# Sensor.net
KiCad netlist of a schematic drawn in Altium Designer
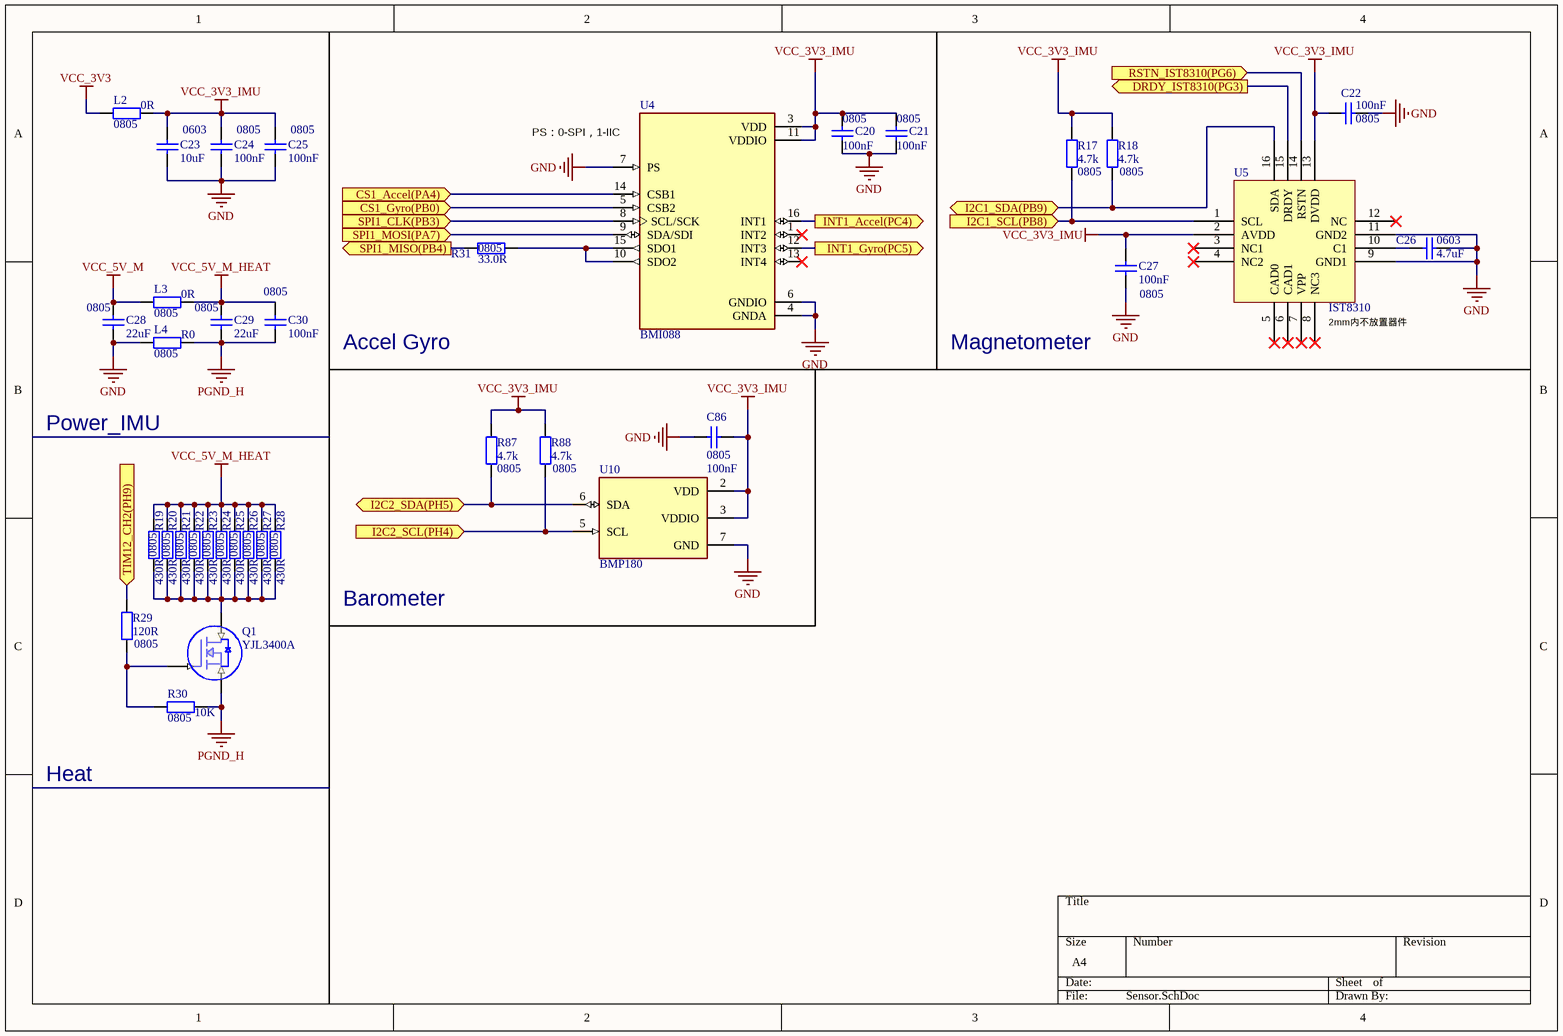
[diagram p0: Sensor.SchDoc]

(export (version "E")
  (design (tool "Eeschema 10.0.6"))
  (components
    (comp (ref "C20")
      (value "0805")
      (footprint "C 0805_M")
      (fields (field (name "ALTIUM_VALUE") "100nF"))
      (libsource (lib "QT") (part "CAP"))
    )
    (comp (ref "C21")
      (value "0805")
      (footprint "C 0805_M")
      (fields (field (name "ALTIUM_VALUE") "100nF"))
      (libsource (lib "QT") (part "CAP"))
    )
    (comp (ref "C22")
      (value "0805")
      (footprint "C 0805_M")
      (fields (field (name "ALTIUM_VALUE") "100nF"))
      (libsource (lib "QT") (part "CAP"))
    )
    (comp (ref "C23")
      (value "0603")
      (footprint "C 0603_L")
      (fields (field (name "ALTIUM_VALUE") "10uF"))
      (libsource (lib "QT") (part "CAP"))
    )
    (comp (ref "C24")
      (value "0805")
      (footprint "C 0805_M")
      (fields (field (name "ALTIUM_VALUE") "100nF"))
      (libsource (lib "QT") (part "CAP"))
    )
    (comp (ref "C25")
      (value "0805")
      (footprint "C 0805_M")
      (fields (field (name "ALTIUM_VALUE") "100nF"))
      (libsource (lib "QT") (part "CAP"))
    )
    (comp (ref "C26")
      (value "0603")
      (footprint "C 0603_M")
      (fields (field (name "ALTIUM_VALUE") "4.7uF"))
      (libsource (lib "QT") (part "CAP"))
    )
    (comp (ref "C27")
      (value "0805")
      (footprint "C 0805_M")
      (fields (field (name "ALTIUM_VALUE") "100nF"))
      (libsource (lib "QT") (part "CAP"))
    )
    (comp (ref "C28")
      (value "0805")
      (footprint "C 0805_L")
      (fields (field (name "ALTIUM_VALUE") "22uF"))
      (libsource (lib "QT") (part "CAP"))
    )
    (comp (ref "C29")
      (value "0805")
      (footprint "C 0805_L")
      (fields (field (name "ALTIUM_VALUE") "22uF"))
      (libsource (lib "QT") (part "CAP"))
    )
    (comp (ref "C30")
      (value "0805")
      (footprint "C 0805_M")
      (fields (field (name "ALTIUM_VALUE") "100nF"))
      (libsource (lib "QT") (part "CAP"))
    )
    (comp (ref "C86")
      (value "0805")
      (footprint "C 0805_M")
      (fields (field (name "ALTIUM_VALUE") "100nF"))
      (libsource (lib "QT") (part "CAP"))
    )
    (comp (ref "L2")
      (value "0805")
      (footprint "R 0805_L")
      (description "Resistor")
      (fields (field (name "ALTIUM_VALUE") "0R") (field (name "PUBLISHER") "Altium Limited"))
      (libsource (lib "") (part "RES2_2"))
    )
    (comp (ref "L3")
      (value "0805")
      (footprint "R 0805_L")
      (description "Resistor")
      (fields (field (name "ALTIUM_VALUE") "0R") (field (name "PUBLISHER") "Altium Limited"))
      (libsource (lib "") (part "RES2_2"))
    )
    (comp (ref "L4")
      (value "0805")
      (footprint "R 0805_L")
      (description "Resistor")
      (fields (field (name "ALTIUM_VALUE") "R0") (field (name "PUBLISHER") "Altium Limited"))
      (libsource (lib "") (part "RES2_2"))
    )
    (comp (ref "Q1") (value "YJL3400A") (footprint "SOT23-3M") (libsource (lib "场效应管及可控硅") (part "MOSFET N")))
    (comp (ref "R17")
      (value "0805")
      (footprint "R 0805_L")
      (description "Resistor")
      (fields (field (name "ALTIUM_VALUE") "4.7k") (field (name "PUBLISHER") "Altium Limited"))
      (libsource (lib "QT") (part "RES2"))
    )
    (comp (ref "R18")
      (value "0805")
      (footprint "R 0805_L")
      (description "Resistor")
      (fields (field (name "ALTIUM_VALUE") "4.7k") (field (name "PUBLISHER") "Altium Limited"))
      (libsource (lib "QT") (part "RES2"))
    )
    (comp (ref "R19")
      (value "0805")
      (footprint "R 0805_L")
      (description "Resistor")
      (fields (field (name "ALTIUM_VALUE") "430R") (field (name "PUBLISHER") "Altium Limited"))
      (libsource (lib "QT") (part "RES2"))
    )
    (comp (ref "R20")
      (value "0805")
      (footprint "R 0805_L")
      (description "Resistor")
      (fields (field (name "ALTIUM_VALUE") "430R") (field (name "PUBLISHER") "Altium Limited"))
      (libsource (lib "QT") (part "RES2"))
    )
    (comp (ref "R21")
      (value "0805")
      (footprint "R 0805_L")
      (description "Resistor")
      (fields (field (name "ALTIUM_VALUE") "430R") (field (name "PUBLISHER") "Altium Limited"))
      (libsource (lib "QT") (part "RES2"))
    )
    (comp (ref "R22")
      (value "0805")
      (footprint "R 0805_L")
      (description "Resistor")
      (fields (field (name "ALTIUM_VALUE") "430R") (field (name "PUBLISHER") "Altium Limited"))
      (libsource (lib "QT") (part "RES2"))
    )
    (comp (ref "R23")
      (value "0805")
      (footprint "R 0805_L")
      (description "Resistor")
      (fields (field (name "ALTIUM_VALUE") "430R") (field (name "PUBLISHER") "Altium Limited"))
      (libsource (lib "QT") (part "RES2"))
    )
    (comp (ref "R24")
      (value "0805")
      (footprint "R 0805_L")
      (description "Resistor")
      (fields (field (name "ALTIUM_VALUE") "430R") (field (name "PUBLISHER") "Altium Limited"))
      (libsource (lib "QT") (part "RES2"))
    )
    (comp (ref "R25")
      (value "0805")
      (footprint "R 0805_L")
      (description "Resistor")
      (fields (field (name "ALTIUM_VALUE") "430R") (field (name "PUBLISHER") "Altium Limited"))
      (libsource (lib "QT") (part "RES2"))
    )
    (comp (ref "R26")
      (value "0805")
      (footprint "R 0805_L")
      (description "Resistor")
      (fields (field (name "ALTIUM_VALUE") "430R") (field (name "PUBLISHER") "Altium Limited"))
      (libsource (lib "QT") (part "RES2"))
    )
    (comp (ref "R27")
      (value "0805")
      (footprint "R 0805_L")
      (description "Resistor")
      (fields (field (name "ALTIUM_VALUE") "430R") (field (name "PUBLISHER") "Altium Limited"))
      (libsource (lib "QT") (part "RES2"))
    )
    (comp (ref "R28")
      (value "0805")
      (footprint "R 0805_L")
      (description "Resistor")
      (fields (field (name "ALTIUM_VALUE") "430R") (field (name "PUBLISHER") "Altium Limited"))
      (libsource (lib "QT") (part "RES2"))
    )
    (comp (ref "R29")
      (value "0805")
      (footprint "R 0805_L")
      (description "Resistor")
      (fields (field (name "ALTIUM_VALUE") "120R") (field (name "PUBLISHER") "Altium Limited"))
      (libsource (lib "") (part "RES2_1"))
    )
    (comp (ref "R30")
      (value "0805")
      (footprint "R 0805_L")
      (description "Resistor")
      (fields (field (name "ALTIUM_VALUE") "10K") (field (name "PUBLISHER") "Altium Limited"))
      (libsource (lib "") (part "RES2_3"))
    )
    (comp (ref "R31")
      (value "0805")
      (footprint "R 0805_L")
      (description "Resistor")
      (fields (field (name "ALTIUM_VALUE") "33.0R") (field (name "PUBLISHER") "Altium Limited"))
      (libsource (lib "") (part "RES2_2"))
    )
    (comp (ref "R87")
      (value "0805")
      (footprint "R 0805_L")
      (description "Resistor")
      (fields (field (name "ALTIUM_VALUE") "4.7k") (field (name "PUBLISHER") "Altium Limited"))
      (libsource (lib "QT") (part "RES2"))
    )
    (comp (ref "R88")
      (value "0805")
      (footprint "R 0805_L")
      (description "Resistor")
      (fields (field (name "ALTIUM_VALUE") "4.7k") (field (name "PUBLISHER") "Altium Limited"))
      (libsource (lib "QT") (part "RES2"))
    )
    (comp (ref "U4")
      (value "BMI088")
      (footprint "PQFN50P450X300X100-16N")
      (description "Accelerometer, Gyroscope, 6 Axis Sensor IÂ²C, SPI Output")
      (fields (field (name "MF") "Bosch Sensortec"))
      (libsource (lib "BMI088") (part "BMI088"))
    )
    (comp (ref "U5") (value "IST8310") (footprint "QFN16") (libsource (lib "常用元件库") (part "IST8310")))
    (comp (ref "U10")
      (value "BMP180")
      (footprint "BMP180")
      (description "Pressure Sensor 4.35PSI ~ 15.95PSI _30kPa ~ 110kPa_ Absolute 16 ~ 19 b 7-VLGA")
      (fields (field (name "MF") "Bosch Sensortec") (field (name "DIGI-KEY_PART_NUMBER") "828-1027-1-ND"))
      (libsource (lib "BMP180") (part "BMP180"))
    )
  )
  (nets
    (net (code "1") (name "/CS1_Accel(PA4)") (class "Default")
      (node (ref "U4") (pin "14") (pinfunction "CSB1_14") (pintype "input"))
    )
    (net (code "2") (name "/CS1_Gyro(PB0)") (class "Default")
      (node (ref "U4") (pin "5") (pinfunction "CSB2_5") (pintype "input"))
    )
    (net (code "3") (name "/DRDY_IST8310(PG3)") (class "Default")
      (node (ref "U5") (pin "15") (pinfunction "DRDY_15") (pintype "passive"))
    )
    (net (code "4") (name "/I2C1_SCL(PB8)") (class "Default")
      (node (ref "R17") (pin "1") (pinfunction "1_1") (pintype "passive"))
      (node (ref "U5") (pin "1") (pinfunction "SCL_1") (pintype "passive"))
    )
    (net (code "5") (name "/I2C1_SDA(PB9)") (class "Default")
      (node (ref "R18") (pin "1") (pinfunction "1_1") (pintype "passive"))
      (node (ref "U5") (pin "16") (pinfunction "SDA_16") (pintype "passive"))
    )
    (net (code "6") (name "/I2C2_SCL(PH4)") (class "Default")
      (node (ref "R88") (pin "1") (pinfunction "1_1") (pintype "passive"))
      (node (ref "U10") (pin "5") (pinfunction "SCL_5") (pintype "input"))
    )
    (net (code "7") (name "/I2C2_SDA(PH5)") (class "Default")
      (node (ref "R87") (pin "1") (pinfunction "1_1") (pintype "passive"))
      (node (ref "U10") (pin "6") (pinfunction "SDA_6") (pintype "bidirectional"))
    )
    (net (code "8") (name "/INT1_Accel(PC4)") (class "Default")
      (node (ref "U4") (pin "16") (pinfunction "INT1_16") (pintype "bidirectional"))
    )
    (net (code "9") (name "/INT1_Gyro(PC5)") (class "Default")
      (node (ref "U4") (pin "12") (pinfunction "INT3_12") (pintype "bidirectional"))
    )
    (net (code "10") (name "/RSTN_IST8310(PG6)") (class "Default")
      (node (ref "U5") (pin "14") (pinfunction "RSTN_14") (pintype "passive"))
    )
    (net (code "11") (name "/SPI1_CLK(PB3)") (class "Default")
      (node (ref "U4") (pin "8") (pinfunction "SCL/SCK_8") (pintype "input"))
    )
    (net (code "12") (name "/SPI1_MISO(PB4)") (class "Default")
      (node (ref "R31") (pin "1") (pinfunction "1_1") (pintype "passive"))
    )
    (net (code "13") (name "/SPI1_MOSI(PA7)") (class "Default")
      (node (ref "U4") (pin "9") (pinfunction "SDA/SDI_9") (pintype "bidirectional"))
    )
    (net (code "14") (name "/TIM12_CH2(PH9)") (class "Default")
      (node (ref "R29") (pin "1") (pinfunction "1_1") (pintype "passive"))
    )
    (net (code "15") (name "GND") (class "Default")
      (node (ref "C20") (pin "1") (pinfunction "1_1") (pintype "passive"))
      (node (ref "C21") (pin "1") (pinfunction "1_1") (pintype "passive"))
      (node (ref "C22") (pin "2") (pinfunction "2_2") (pintype "passive"))
      (node (ref "C23") (pin "1") (pinfunction "1_1") (pintype "passive"))
      (node (ref "C24") (pin "1") (pinfunction "1_1") (pintype "passive"))
      (node (ref "C25") (pin "1") (pinfunction "1_1") (pintype "passive"))
      (node (ref "C26") (pin "2") (pinfunction "2_2") (pintype "passive"))
      (node (ref "C27") (pin "1") (pinfunction "1_1") (pintype "passive"))
      (node (ref "C28") (pin "1") (pinfunction "1_1") (pintype "passive"))
      (node (ref "C86") (pin "2") (pinfunction "2_2") (pintype "passive"))
      (node (ref "L4") (pin "1") (pinfunction "1_1") (pintype "passive"))
      (node (ref "U10") (pin "7") (pinfunction "GND_7") (pintype "power_in"))
      (node (ref "U4") (pin "4") (pinfunction "GNDA_4") (pintype "power_in"))
      (node (ref "U4") (pin "6") (pinfunction "GNDIO_6") (pintype "power_in"))
      (node (ref "U4") (pin "7") (pinfunction "PS_7") (pintype "input"))
      (node (ref "U5") (pin "11") (pinfunction "GND2_11") (pintype "passive"))
      (node (ref "U5") (pin "9") (pinfunction "GND1_9") (pintype "passive"))
    )
    (net (code "16") (name "Net-(Q1-D)") (class "Default")
      (node (ref "Q1") (pin "3") (pinfunction "D_3") (pintype "input"))
      (node (ref "R19") (pin "1") (pinfunction "1_1") (pintype "passive"))
      (node (ref "R20") (pin "1") (pinfunction "1_1") (pintype "passive"))
      (node (ref "R21") (pin "1") (pinfunction "1_1") (pintype "passive"))
      (node (ref "R22") (pin "1") (pinfunction "1_1") (pintype "passive"))
      (node (ref "R23") (pin "1") (pinfunction "1_1") (pintype "passive"))
      (node (ref "R24") (pin "1") (pinfunction "1_1") (pintype "passive"))
      (node (ref "R25") (pin "1") (pinfunction "1_1") (pintype "passive"))
      (node (ref "R26") (pin "1") (pinfunction "1_1") (pintype "passive"))
      (node (ref "R27") (pin "1") (pinfunction "1_1") (pintype "passive"))
      (node (ref "R28") (pin "1") (pinfunction "1_1") (pintype "passive"))
    )
    (net (code "17") (name "Net-(Q1-G)") (class "Default")
      (node (ref "Q1") (pin "1") (pinfunction "G_1") (pintype "input"))
      (node (ref "R29") (pin "2") (pinfunction "2_2") (pintype "passive"))
      (node (ref "R30") (pin "2") (pinfunction "2_2") (pintype "passive"))
    )
    (net (code "18") (name "Net-(U4-SDO1)") (class "Default")
      (node (ref "R31") (pin "2") (pinfunction "2_2") (pintype "passive"))
      (node (ref "U4") (pin "10") (pinfunction "SDO2_10") (pintype "output"))
      (node (ref "U4") (pin "15") (pinfunction "SDO1_15") (pintype "output"))
    )
    (net (code "19") (name "Net-(U5-C1)") (class "Default")
      (node (ref "C26") (pin "1") (pinfunction "1_1") (pintype "passive"))
      (node (ref "U5") (pin "10") (pinfunction "C1_10") (pintype "passive"))
    )
    (net (code "20") (name "PGND_H") (class "Default")
      (node (ref "C29") (pin "1") (pinfunction "1_1") (pintype "passive"))
      (node (ref "C30") (pin "1") (pinfunction "1_1") (pintype "passive"))
      (node (ref "L4") (pin "2") (pinfunction "2_2") (pintype "passive"))
      (node (ref "Q1") (pin "2") (pinfunction "S_2") (pintype "input"))
      (node (ref "R30") (pin "1") (pinfunction "1_1") (pintype "passive"))
    )
    (net (code "21") (name "VCC_3V3") (class "Default")
      (node (ref "L2") (pin "1") (pinfunction "1_1") (pintype "passive"))
    )
    (net (code "22") (name "VCC_3V3_IMU") (class "Default")
      (node (ref "C20") (pin "2") (pinfunction "2_2") (pintype "passive"))
      (node (ref "C21") (pin "2") (pinfunction "2_2") (pintype "passive"))
      (node (ref "C22") (pin "1") (pinfunction "1_1") (pintype "passive"))
      (node (ref "C23") (pin "2") (pinfunction "2_2") (pintype "passive"))
      (node (ref "C24") (pin "2") (pinfunction "2_2") (pintype "passive"))
      (node (ref "C25") (pin "2") (pinfunction "2_2") (pintype "passive"))
      (node (ref "C27") (pin "2") (pinfunction "2_2") (pintype "passive"))
      (node (ref "C86") (pin "1") (pinfunction "1_1") (pintype "passive"))
      (node (ref "L2") (pin "2") (pinfunction "2_2") (pintype "passive"))
      (node (ref "R17") (pin "2") (pinfunction "2_2") (pintype "passive"))
      (node (ref "R18") (pin "2") (pinfunction "2_2") (pintype "passive"))
      (node (ref "R87") (pin "2") (pinfunction "2_2") (pintype "passive"))
      (node (ref "R88") (pin "2") (pinfunction "2_2") (pintype "passive"))
      (node (ref "U10") (pin "2") (pinfunction "VDD_2") (pintype "power_in"))
      (node (ref "U10") (pin "3") (pinfunction "VDDIO_3") (pintype "power_in"))
      (node (ref "U4") (pin "11") (pinfunction "VDDIO_11") (pintype "power_in"))
      (node (ref "U4") (pin "3") (pinfunction "VDD_3") (pintype "power_in"))
      (node (ref "U5") (pin "13") (pinfunction "DVDD_13") (pintype "passive"))
      (node (ref "U5") (pin "2") (pinfunction "AVDD_2") (pintype "passive"))
    )
    (net (code "23") (name "VCC_5V_M") (class "Default")
      (node (ref "C28") (pin "2") (pinfunction "2_2") (pintype "passive"))
      (node (ref "L3") (pin "1") (pinfunction "1_1") (pintype "passive"))
    )
    (net (code "24") (name "VCC_5V_M_HEAT") (class "Default")
      (node (ref "C29") (pin "2") (pinfunction "2_2") (pintype "passive"))
      (node (ref "C30") (pin "2") (pinfunction "2_2") (pintype "passive"))
      (node (ref "L3") (pin "2") (pinfunction "2_2") (pintype "passive"))
      (node (ref "R19") (pin "2") (pinfunction "2_2") (pintype "passive"))
      (node (ref "R20") (pin "2") (pinfunction "2_2") (pintype "passive"))
      (node (ref "R21") (pin "2") (pinfunction "2_2") (pintype "passive"))
      (node (ref "R22") (pin "2") (pinfunction "2_2") (pintype "passive"))
      (node (ref "R23") (pin "2") (pinfunction "2_2") (pintype "passive"))
      (node (ref "R24") (pin "2") (pinfunction "2_2") (pintype "passive"))
      (node (ref "R25") (pin "2") (pinfunction "2_2") (pintype "passive"))
      (node (ref "R26") (pin "2") (pinfunction "2_2") (pintype "passive"))
      (node (ref "R27") (pin "2") (pinfunction "2_2") (pintype "passive"))
      (node (ref "R28") (pin "2") (pinfunction "2_2") (pintype "passive"))
    )
    (net (code "25") (name "unconnected-(U4-INT2-Pad1)") (class "Default")
      (node (ref "U4") (pin "1") (pinfunction "INT2_1") (pintype "bidirectional+no_connect"))
    )
    (net (code "26") (name "unconnected-(U4-INT4-Pad13)") (class "Default")
      (node (ref "U4") (pin "13") (pinfunction "INT4_13") (pintype "bidirectional+no_connect"))
    )
    (net (code "27") (name "unconnected-(U5-CAD0-Pad5)") (class "Default")
      (node (ref "U5") (pin "5") (pinfunction "CAD0_5") (pintype "passive+no_connect"))
    )
    (net (code "28") (name "unconnected-(U5-CAD1-Pad6)") (class "Default")
      (node (ref "U5") (pin "6") (pinfunction "CAD1_6") (pintype "passive+no_connect"))
    )
    (net (code "29") (name "unconnected-(U5-NC-Pad12)") (class "Default")
      (node (ref "U5") (pin "12") (pinfunction "NC_12") (pintype "passive+no_connect"))
    )
    (net (code "30") (name "unconnected-(U5-NC1-Pad3)") (class "Default")
      (node (ref "U5") (pin "3") (pinfunction "NC1_3") (pintype "passive+no_connect"))
    )
    (net (code "31") (name "unconnected-(U5-NC2-Pad4)") (class "Default")
      (node (ref "U5") (pin "4") (pinfunction "NC2_4") (pintype "passive+no_connect"))
    )
    (net (code "32") (name "unconnected-(U5-NC3-Pad8)") (class "Default")
      (node (ref "U5") (pin "8") (pinfunction "NC3_8") (pintype "passive+no_connect"))
    )
    (net (code "33") (name "unconnected-(U5-VPP-Pad7)") (class "Default")
      (node (ref "U5") (pin "7") (pinfunction "VPP_7") (pintype "passive+no_connect"))
    )
  )
)
